# EEZ_DIB_AUX_PS_r2B2.net
KiCad netlist of a schematic drawn in EAGLE
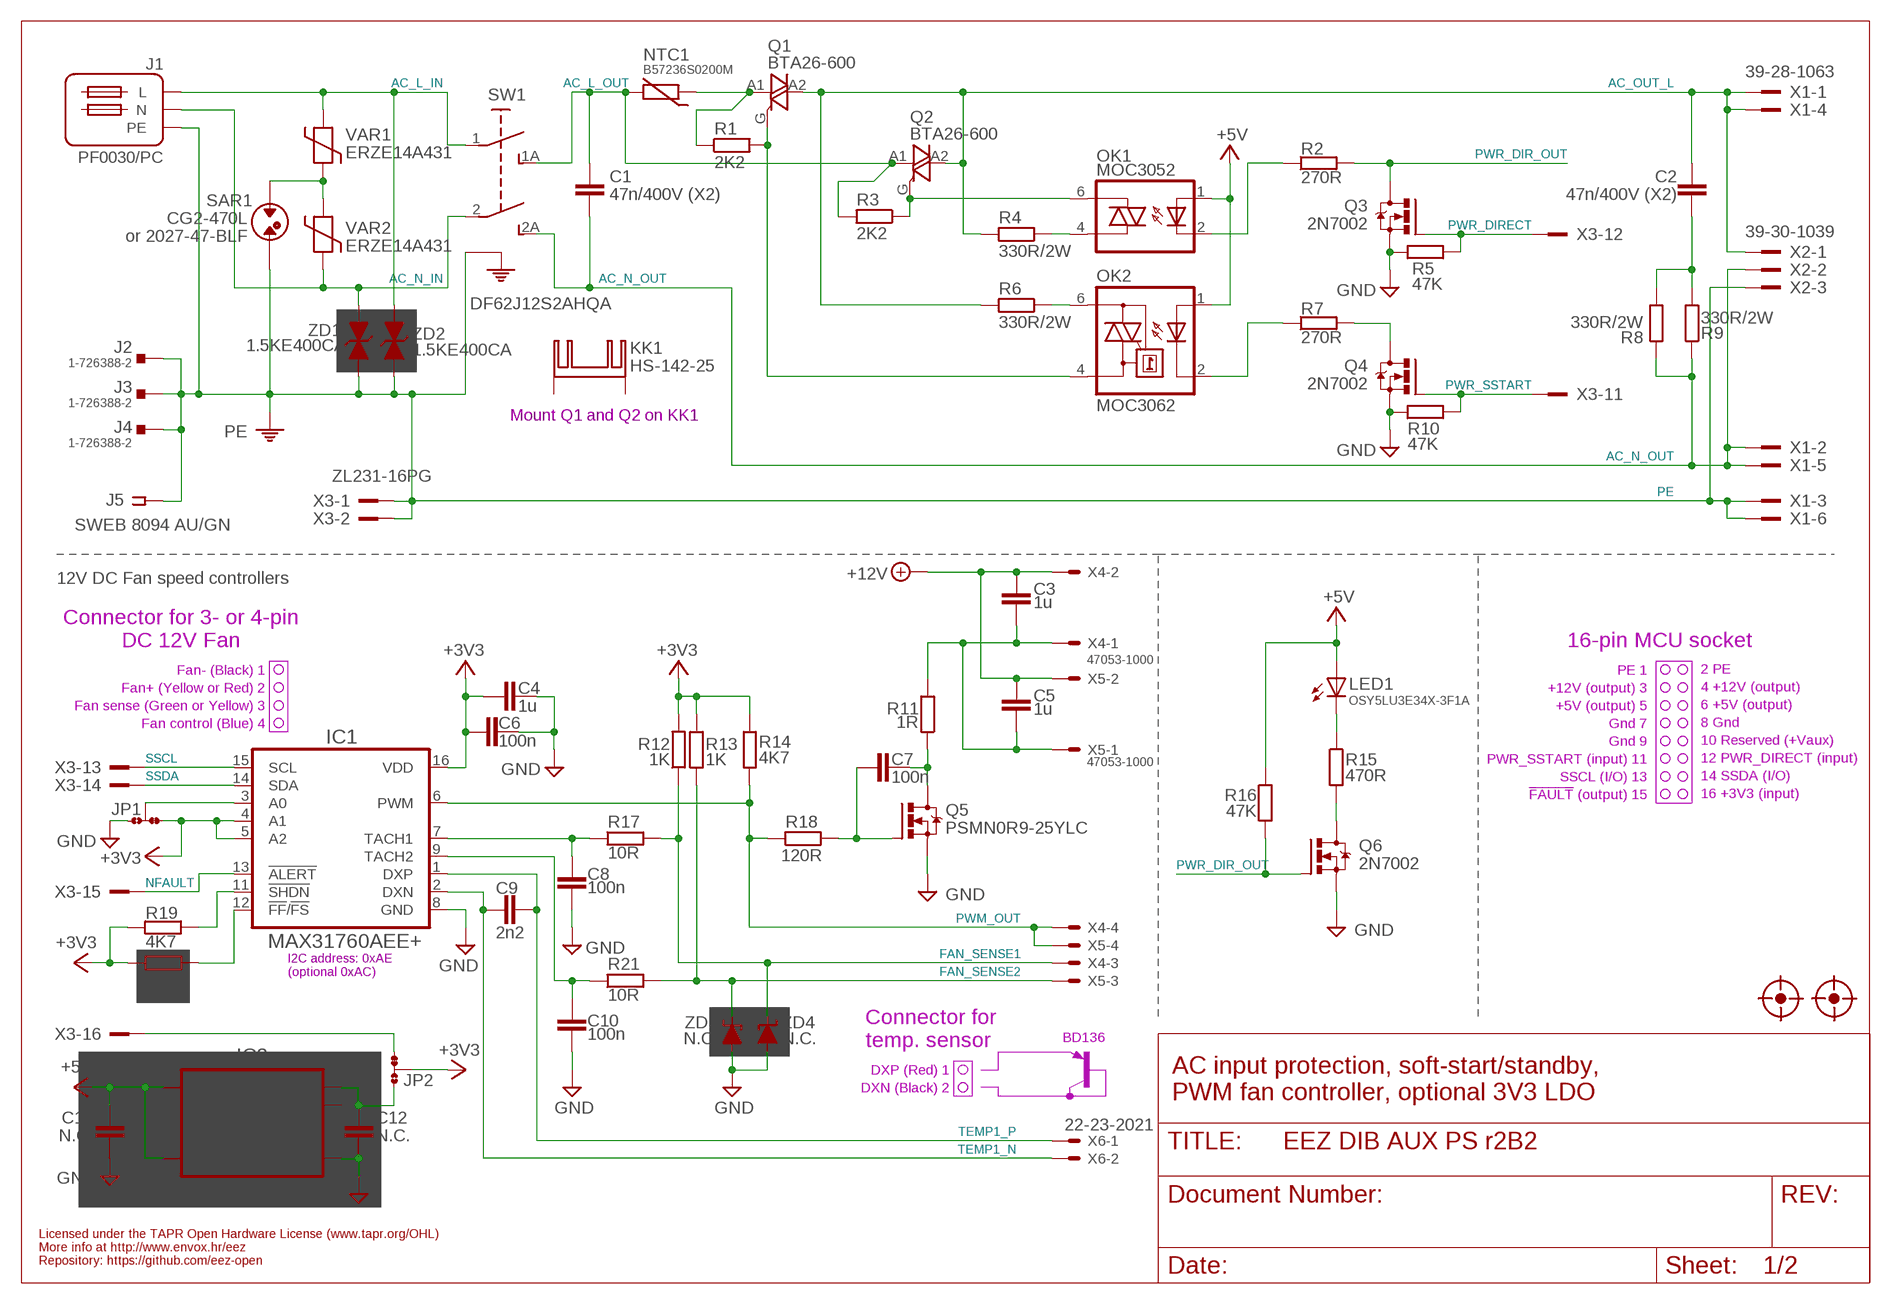
[diagram p0: schematic, sheet 1]
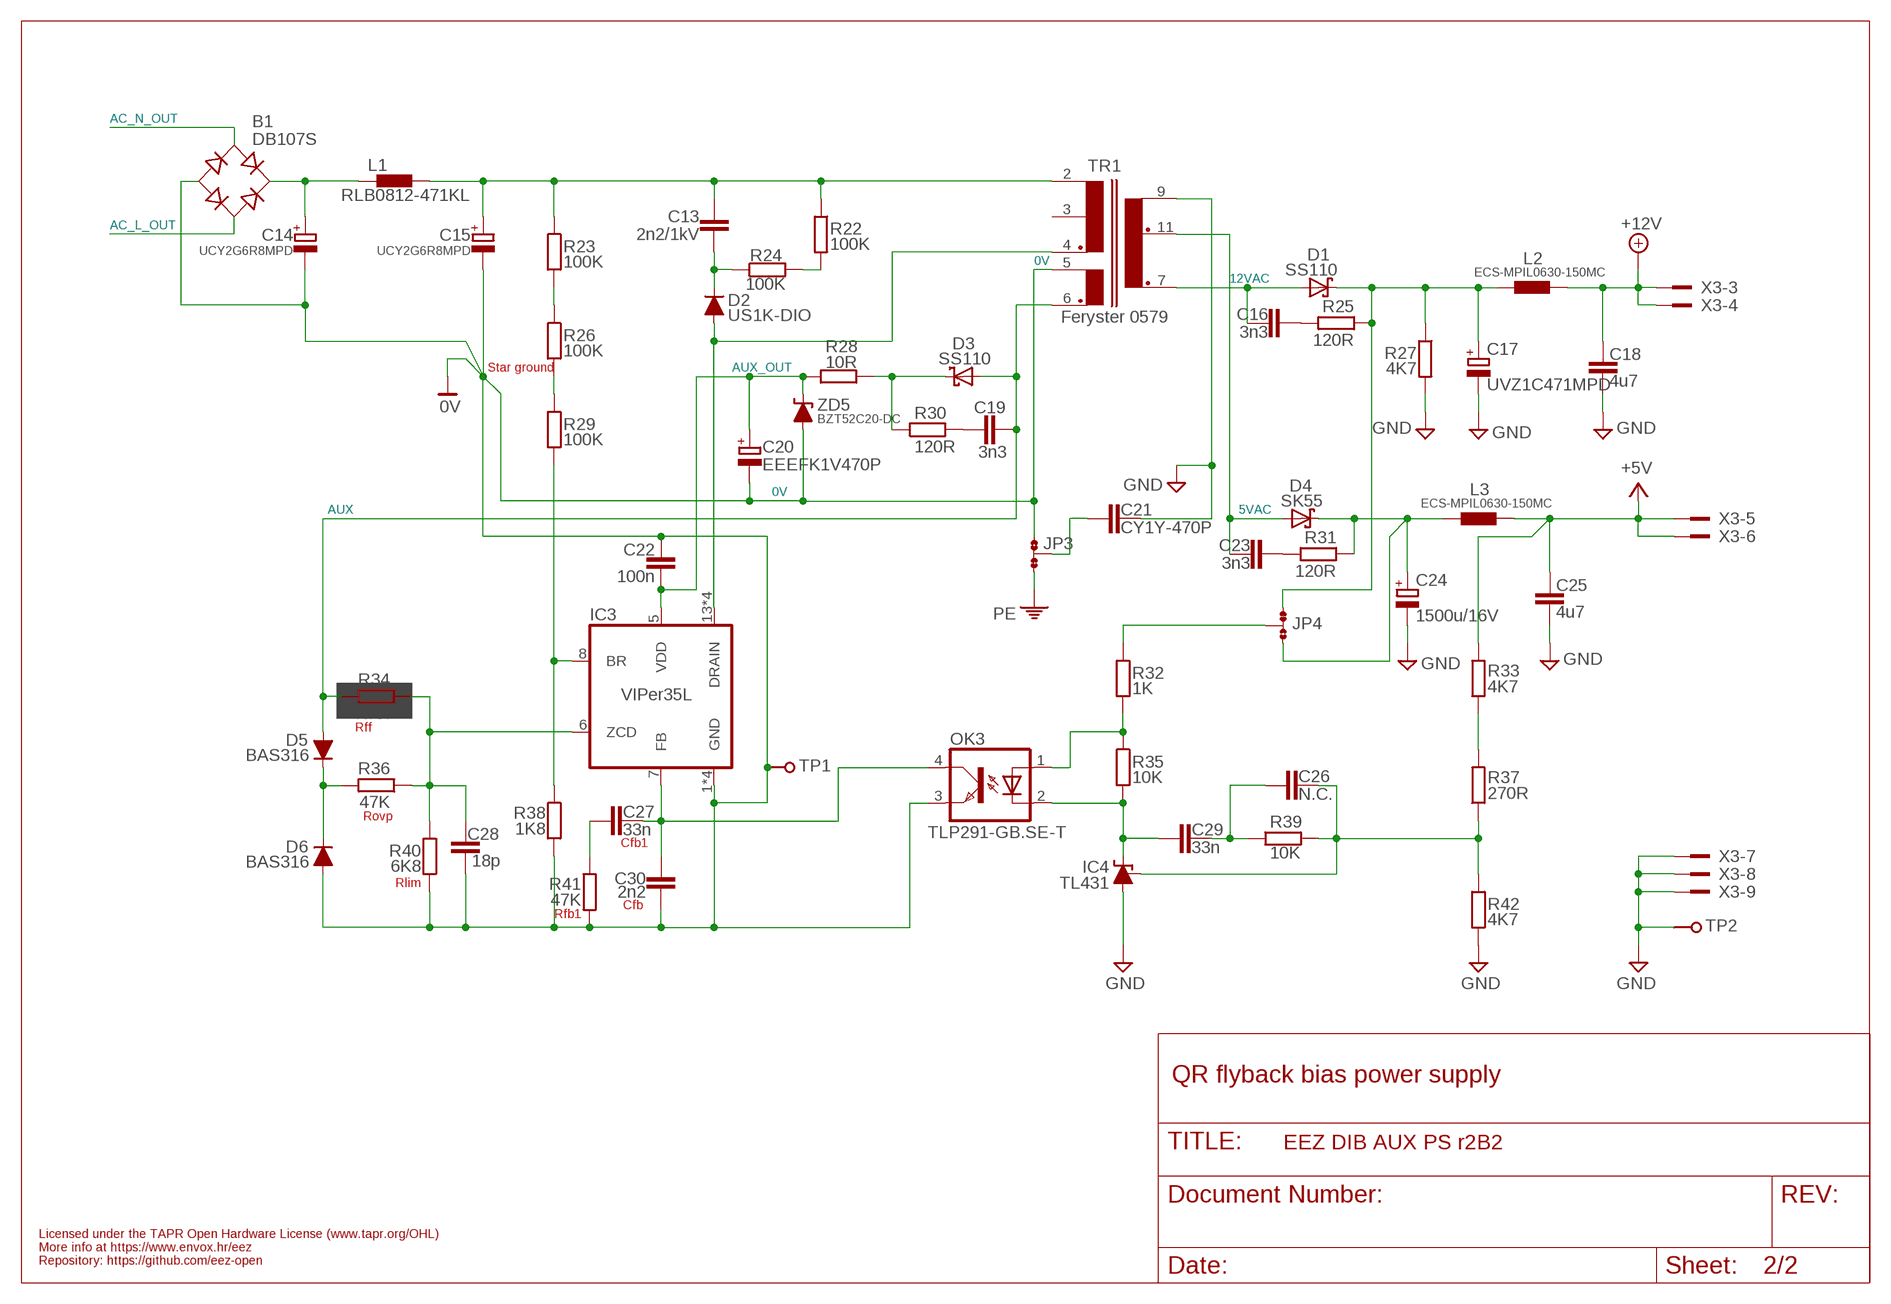
[diagram p1: schematic, sheet 2]

(export (version "E")
  (design (tool "Eeschema 10.0.6"))
  (components
    (comp (ref "B1")
      (value "DB107S")
      (footprint "eagle-import:DBS")
      (libsource (lib "eagle-import") (part "DB?GS107"))
    )
    (comp (ref "C13")
      (value "2n2/1kV")
      (footprint "eagle-import:C1210")
      (libsource (lib "eagle-import") (part "C-EUC1210"))
    )
    (comp (ref "C14")
      (value "UCY2G6R8MPD")
      (footprint "eagle-import:ECAP5_10.5")
      (libsource (lib "eagle-import") (part "ECAP5G_10.5MM"))
    )
    (comp (ref "C15")
      (value "UCY2G6R8MPD")
      (footprint "eagle-import:ECAP5_10.5")
      (libsource (lib "eagle-import") (part "ECAP5G_10.5MM"))
    )
    (comp (ref "C16")
      (value "3n3")
      (footprint "eagle-import:C0805")
      (libsource (lib "eagle-import") (part "C-EUC0805"))
    )
    (comp (ref "C17")
      (value "UVZ1C471MPD")
      (footprint "eagle-import:ECAP3.5_8")
      (libsource (lib "eagle-import") (part "ECAP3.5G_8MM"))
    )
    (comp (ref "C18")
      (value "4u7")
      (footprint "eagle-import:C1210")
      (libsource (lib "eagle-import") (part "C-EUC1210"))
    )
    (comp (ref "C19")
      (value "3n3")
      (footprint "eagle-import:C0805")
      (libsource (lib "eagle-import") (part "C-EUC0805"))
    )
    (comp (ref "C20")
      (value "EEEFK1V470P")
      (footprint "eagle-import:CAPAE660X610N")
      (libsource (lib "eagle-import") (part "ECAPPANASONIC_H"))
    )
    (comp (ref "C21")
      (value "CY1Y-470P")
      (footprint "eagle-import:CY075-032X103")
      (libsource (lib "eagle-import") (part "C-EUCY"))
    )
    (comp (ref "C22")
      (value "100n")
      (footprint "eagle-import:C0603")
      (libsource (lib "eagle-import") (part "C-EUC0603"))
    )
    (comp (ref "C23")
      (value "3n3")
      (footprint "eagle-import:C0805")
      (libsource (lib "eagle-import") (part "C-EUC0805"))
    )
    (comp (ref "C24")
      (value "1500u/16V")
      (footprint "eagle-import:ECAP5_13")
      (libsource (lib "eagle-import") (part "ECAP5G_13MM"))
    )
    (comp (ref "C25")
      (value "4u7")
      (footprint "eagle-import:C1210")
      (libsource (lib "eagle-import") (part "C-EUC1210"))
    )
    (comp (ref "C26")
      (value "N.C.")
      (footprint "eagle-import:C0805")
      (libsource (lib "eagle-import") (part "C-EUC0805"))
    )
    (comp (ref "C27")
      (value "33n")
      (footprint "eagle-import:C0805")
      (libsource (lib "eagle-import") (part "C-EUC0805"))
    )
    (comp (ref "C28")
      (value "18p")
      (footprint "eagle-import:C0603")
      (libsource (lib "eagle-import") (part "C-EUC0603"))
    )
    (comp (ref "C29")
      (value "33n")
      (footprint "eagle-import:C0805")
      (libsource (lib "eagle-import") (part "C-EUC0805"))
    )
    (comp (ref "C30")
      (value "2n2")
      (footprint "eagle-import:C0805")
      (libsource (lib "eagle-import") (part "C-EUC0805"))
    )
    (comp (ref "D1")
      (value "SS110")
      (footprint "eagle-import:SMB")
      (libsource (lib "eagle-import") (part "SCHOTTKYSMB"))
    )
    (comp (ref "D2")
      (value "US1K-DIO")
      (footprint "eagle-import:DO214AA")
      (libsource (lib "eagle-import") (part "DIODEDO214AA"))
    )
    (comp (ref "D3")
      (value "SS110")
      (footprint "eagle-import:SMB")
      (libsource (lib "eagle-import") (part "SCHOTTKYSMB"))
    )
    (comp (ref "D4")
      (value "SK55")
      (footprint "eagle-import:SMB")
      (libsource (lib "eagle-import") (part "SCHOTTKYSMB"))
    )
    (comp (ref "D5")
      (value "BAS316")
      (footprint "eagle-import:SOD323-R")
      (libsource (lib "eagle-import") (part "DIODESOD323R"))
    )
    (comp (ref "D6")
      (value "BAS316")
      (footprint "eagle-import:SOD323-R")
      (libsource (lib "eagle-import") (part "DIODESOD323R"))
    )
    (comp (ref "IC3")
      (value "VIPer35L")
      (footprint "eagle-import:SOIC-16")
      (libsource (lib "eagle-import") (part "VIPER35"))
    )
    (comp (ref "IC4")
      (value "TL431")
      (footprint "eagle-import:SOT103P240X110-3N")
      (libsource (lib "eagle-import") (part "TL431"))
    )
    (comp (ref "JP3")
      (value "JP3-CUT")
      (footprint "eagle-import:JP3-CUT")
      (libsource (lib "eagle-import") (part "JP3-CUT"))
    )
    (comp (ref "JP4")
      (value "JP3-CUT")
      (footprint "eagle-import:JP3-CUT")
      (libsource (lib "eagle-import") (part "JP3-CUT"))
    )
    (comp (ref "L1")
      (value "RLB0812-471KL")
      (footprint "eagle-import:FERSYTER_DSZ6")
      (libsource (lib "eagle-import") (part "FERYSTER_DSZ6"))
    )
    (comp (ref "L2")
      (value "ECS-MPIL0630-150MC")
      (footprint "eagle-import:DE0704")
      (libsource (lib "eagle-import") (part "DE0704"))
    )
    (comp (ref "L3")
      (value "ECS-MPIL0630-150MC")
      (footprint "eagle-import:DE0704")
      (libsource (lib "eagle-import") (part "DE0704"))
    )
    (comp (ref "OK3")
      (value "TLP291-GB.SE-T")
      (footprint "eagle-import:SO4")
      (libsource (lib "eagle-import") (part "TLP291"))
    )
    (comp (ref "R22")
      (value "100K")
      (footprint "eagle-import:R1206")
      (libsource (lib "eagle-import") (part "R-EU_R1206"))
    )
    (comp (ref "R23")
      (value "100K")
      (footprint "eagle-import:R1206")
      (libsource (lib "eagle-import") (part "R-EU_R1206"))
    )
    (comp (ref "R24")
      (value "100K")
      (footprint "eagle-import:R1206")
      (libsource (lib "eagle-import") (part "R-EU_R1206"))
    )
    (comp (ref "R25")
      (value "120R")
      (footprint "eagle-import:R0805")
      (libsource (lib "eagle-import") (part "R-EU_R0805"))
    )
    (comp (ref "R26")
      (value "100K")
      (footprint "eagle-import:R1206")
      (libsource (lib "eagle-import") (part "R-EU_R1206"))
    )
    (comp (ref "R27")
      (value "4K7")
      (footprint "eagle-import:R0805")
      (libsource (lib "eagle-import") (part "R-EU_R0805"))
    )
    (comp (ref "R28")
      (value "10R")
      (footprint "eagle-import:R0805")
      (libsource (lib "eagle-import") (part "R-EU_R0805"))
    )
    (comp (ref "R29")
      (value "100K")
      (footprint "eagle-import:R1206")
      (libsource (lib "eagle-import") (part "R-EU_R1206"))
    )
    (comp (ref "R30")
      (value "120R")
      (footprint "eagle-import:R0805")
      (libsource (lib "eagle-import") (part "R-EU_R0805"))
    )
    (comp (ref "R31")
      (value "120R")
      (footprint "eagle-import:R0805")
      (libsource (lib "eagle-import") (part "R-EU_R0805"))
    )
    (comp (ref "R32")
      (value "1K")
      (footprint "eagle-import:R0805")
      (libsource (lib "eagle-import") (part "R-EU_R0805"))
    )
    (comp (ref "R33")
      (value "4K7")
      (footprint "eagle-import:R0805")
      (libsource (lib "eagle-import") (part "R-EU_R0805"))
    )
    (comp (ref "R34")
      (value "N.C.")
      (footprint "eagle-import:R0805")
      (libsource (lib "eagle-import") (part "R-EU_R0805"))
    )
    (comp (ref "R35")
      (value "10K")
      (footprint "eagle-import:R0805")
      (libsource (lib "eagle-import") (part "R-EU_R0805"))
    )
    (comp (ref "R36")
      (value "47K")
      (footprint "eagle-import:R0805")
      (libsource (lib "eagle-import") (part "R-EU_R0805"))
    )
    (comp (ref "R37")
      (value "270R")
      (footprint "eagle-import:R0805")
      (libsource (lib "eagle-import") (part "R-EU_R0805"))
    )
    (comp (ref "R38")
      (value "1K8")
      (footprint "eagle-import:R0805")
      (libsource (lib "eagle-import") (part "R-EU_R0805"))
    )
    (comp (ref "R39")
      (value "10K")
      (footprint "eagle-import:R0805")
      (libsource (lib "eagle-import") (part "R-EU_R0805"))
    )
    (comp (ref "R40")
      (value "6K8")
      (footprint "eagle-import:R0805")
      (libsource (lib "eagle-import") (part "R-EU_R0805"))
    )
    (comp (ref "R41")
      (value "47K")
      (footprint "eagle-import:R0805")
      (libsource (lib "eagle-import") (part "R-EU_R0805"))
    )
    (comp (ref "R42")
      (value "4K7")
      (footprint "eagle-import:R0805")
      (libsource (lib "eagle-import") (part "R-EU_R0805"))
    )
    (comp (ref "TP1")
      (value "PCB_TEST_TABSHIELD")
      (footprint "eagle-import:PCB_SHIELD_TAB")
      (libsource (lib "eagle-import") (part "PCB_TEST_TABSHIELD"))
    )
    (comp (ref "TP2")
      (value "PCB_TEST_TABSHIELD")
      (footprint "eagle-import:PCB_SHIELD_TAB")
      (libsource (lib "eagle-import") (part "PCB_TEST_TABSHIELD"))
    )
    (comp (ref "TR1")
      (value "Feryster 0579")
      (footprint "eagle-import:FERYSTER_0579")
      (libsource (lib "eagle-import") (part "FERYSTER_0579"))
    )
    (comp (ref "X3")
      (value "ZL231-16PG")
      (footprint "eagle-import:IDC-16PIN")
      (libsource (lib "eagle-import") (part "IDC-16PIN"))
    )
    (comp (ref "ZD5")
      (value "BZT52C20-DC")
      (footprint "eagle-import:SOD123")
      (libsource (lib "eagle-import") (part "ZENER-DIODESOD123"))
    )
    (comp (ref "C1")
      (value "47n/400V (X2)")
      (footprint "eagle-import:C102-054X133")
      (libsource (lib "eagle-import") (part "C-EU102-054X133"))
    )
    (comp (ref "C2")
      (value "47n/400V (X2)")
      (footprint "eagle-import:C102-054X133")
      (libsource (lib "eagle-import") (part "C-EU102-054X133"))
    )
    (comp (ref "C3")
      (value "1u")
      (footprint "eagle-import:C0805")
      (libsource (lib "eagle-import") (part "C-EUC0805"))
    )
    (comp (ref "C4")
      (value "1u")
      (footprint "eagle-import:C0805")
      (libsource (lib "eagle-import") (part "C-EUC0805"))
    )
    (comp (ref "C5")
      (value "1u")
      (footprint "eagle-import:C0805")
      (libsource (lib "eagle-import") (part "C-EUC0805"))
    )
    (comp (ref "C6")
      (value "100n")
      (footprint "eagle-import:C0603")
      (libsource (lib "eagle-import") (part "C-EUC0603"))
    )
    (comp (ref "C7")
      (value "100n")
      (footprint "eagle-import:C0805")
      (libsource (lib "eagle-import") (part "C-EUC0805"))
    )
    (comp (ref "C8")
      (value "100n")
      (footprint "eagle-import:C0603")
      (libsource (lib "eagle-import") (part "C-EUC0603"))
    )
    (comp (ref "C9")
      (value "2n2")
      (footprint "eagle-import:C0805")
      (libsource (lib "eagle-import") (part "C-EUC0805"))
    )
    (comp (ref "C10")
      (value "100n")
      (footprint "eagle-import:C0603")
      (libsource (lib "eagle-import") (part "C-EUC0603"))
    )
    (comp (ref "C11")
      (value "N.C.")
      (footprint "eagle-import:C0805")
      (libsource (lib "eagle-import") (part "C-EUC0805"))
    )
    (comp (ref "C12")
      (value "N.C.")
      (footprint "eagle-import:C0805")
      (libsource (lib "eagle-import") (part "C-EUC0805"))
    )
    (comp (ref "FM1")
      (value "FIDUCIAL")
      (footprint "eagle-import:FIDUCIAL")
      (libsource (lib "eagle-import") (part "FIDUCIAL"))
    )
    (comp (ref "FM2")
      (value "FIDUCIAL")
      (footprint "eagle-import:FIDUCIAL")
      (libsource (lib "eagle-import") (part "FIDUCIAL"))
    )
    (comp (ref "IC1")
      (value "MAX31760AEE+")
      (footprint "eagle-import:DBQ16")
      (libsource (lib "eagle-import") (part "MAX31760AEE+"))
    )
    (comp (ref "IC2")
      (value "LP2985")
      (footprint "eagle-import:SOT95P270X145-5N")
      (libsource (lib "eagle-import") (part "LP2985"))
    )
    (comp (ref "J1")
      (value "PF0030/PC")
      (footprint "eagle-import:PF0030_PC")
      (libsource (lib "eagle-import") (part "PF0030/PC"))
    )
    (comp (ref "J2")
      (value "1-726388-2")
      (footprint "eagle-import:PCB_TAB-4.8MM")
      (libsource (lib "eagle-import") (part "PCB_TAB4.8MM"))
    )
    (comp (ref "J3")
      (value "1-726388-2")
      (footprint "eagle-import:PCB_TAB-4.8MM")
      (libsource (lib "eagle-import") (part "PCB_TAB4.8MM"))
    )
    (comp (ref "J4")
      (value "1-726388-2")
      (footprint "eagle-import:PCB_TAB-4.8MM")
      (libsource (lib "eagle-import") (part "PCB_TAB4.8MM"))
    )
    (comp (ref "J5")
      (value "SWEB 8094 AU/GN")
      (footprint "eagle-import:S16N-PC")
      (libsource (lib "eagle-import") (part "BINDING_POSTCLIFF"))
    )
    (comp (ref "JP1")
      (value "JP3-CUT")
      (footprint "eagle-import:JP3-CUT")
      (libsource (lib "eagle-import") (part "JP3-CUT"))
    )
    (comp (ref "JP2")
      (value "JP3-CUT")
      (footprint "eagle-import:JP3-CUT")
      (libsource (lib "eagle-import") (part "JP3-CUT"))
    )
    (comp (ref "KK1")
      (value "HS-142-25")
      (footprint "eagle-import:SK129")
      (libsource (lib "eagle-import") (part "SK129-PAD"))
    )
    (comp (ref "LED1")
      (value "OSY5LU3E34X-3F1A")
      (footprint "eagle-import:OSG8")
      (libsource (lib "eagle-import") (part "LEDOSG8"))
    )
    (comp (ref "NTC1")
      (value "B57236S0200M")
      (footprint "eagle-import:NTC_11.5X6_RM5")
      (libsource (lib "eagle-import") (part "NTC11.5X6"))
    )
    (comp (ref "OK1")
      (value "MOC3052")
      (footprint "eagle-import:DIL6-SMD")
      (libsource (lib "eagle-import") (part "MOC305X"))
    )
    (comp (ref "OK2")
      (value "MOC3062")
      (footprint "eagle-import:DIL6-SMD")
      (fields
        (field (name "MF") "FAIRCHILD SEMICONDUCTOR")
        (field (name "MPN") "MOC3033S-M")
        (field (name "MF_1") "FAIRCHILD SEMICONDUCTOR")
        (field (name "MPN_1") "MOC3033S-M")
        (field (name "OC_FARNELL") "unknown")
        (field (name "OC_NEWARK") "05C2878")
      )
      (libsource (lib "eagle-import") (part "MOC30S33"))
    )
    (comp (ref "Q1")
      (value "BTA26-600")
      (footprint "eagle-import:TOP3S-1")
      (libsource (lib "eagle-import") (part "BTA26-V"))
    )
    (comp (ref "Q2")
      (value "BTA26-600")
      (footprint "eagle-import:TOP3S-1")
      (libsource (lib "eagle-import") (part "BTA26-V"))
    )
    (comp (ref "Q3")
      (value "2N7002")
      (footprint "eagle-import:SOT103P240X110-3N")
      (fields (field (name "MPN") "2N7002-7-F"))
      (libsource (lib "eagle-import") (part "2N7002"))
    )
    (comp (ref "Q4")
      (value "2N7002")
      (footprint "eagle-import:SOT103P240X110-3N")
      (fields (field (name "MPN") "2N7002-7-F"))
      (libsource (lib "eagle-import") (part "2N7002"))
    )
    (comp (ref "Q5")
      (value "PSMN0R9-25YLC")
      (footprint "eagle-import:SOT669")
      (libsource (lib "eagle-import") (part "N-MOSFETLFPAK"))
    )
    (comp (ref "Q6")
      (value "2N7002")
      (footprint "eagle-import:SOT103P240X110-3N")
      (fields
        (field (name "MPN") "2N7002-7-F")
        (field (name "MPN_1") "2N7002-7-F")
        (field (name "OC_FARNELL") "1713823")
        (field (name "OC_NEWARK") "25R5679")
        (field (name "PACKAGE") "SOT-23-3")
        (field (name "SUPPLIER") "DIODES INC.")
      )
      (libsource (lib "eagle-import") (part "2N7002"))
    )
    (comp (ref "R1")
      (value "2K2")
      (footprint "eagle-import:R0805")
      (libsource (lib "eagle-import") (part "R-EU_R0805"))
    )
    (comp (ref "R2")
      (value "270R")
      (footprint "eagle-import:R0805")
      (libsource (lib "eagle-import") (part "R-EU_R0805"))
    )
    (comp (ref "R3")
      (value "2K2")
      (footprint "eagle-import:R0805")
      (libsource (lib "eagle-import") (part "R-EU_R0805"))
    )
    (comp (ref "R4")
      (value "330R/2W")
      (footprint "eagle-import:R2512")
      (libsource (lib "eagle-import") (part "R-EU_R2512"))
    )
    (comp (ref "R5")
      (value "47K")
      (footprint "eagle-import:R0805")
      (libsource (lib "eagle-import") (part "R-EU_R0805"))
    )
    (comp (ref "R6")
      (value "330R/2W")
      (footprint "eagle-import:R2512")
      (libsource (lib "eagle-import") (part "R-EU_R2512"))
    )
    (comp (ref "R7")
      (value "270R")
      (footprint "eagle-import:R0805")
      (libsource (lib "eagle-import") (part "R-EU_R0805"))
    )
    (comp (ref "R8")
      (value "330R/2W")
      (footprint "eagle-import:R2512")
      (libsource (lib "eagle-import") (part "R-EU_R2512"))
    )
    (comp (ref "R9")
      (value "330R/2W")
      (footprint "eagle-import:R2512")
      (libsource (lib "eagle-import") (part "R-EU_R2512"))
    )
    (comp (ref "R10")
      (value "47K")
      (footprint "eagle-import:R0805")
      (libsource (lib "eagle-import") (part "R-EU_R0805"))
    )
    (comp (ref "R11")
      (value "1R")
      (footprint "eagle-import:R0805")
      (libsource (lib "eagle-import") (part "R-EU_R0805"))
    )
    (comp (ref "R12")
      (value "1K")
      (footprint "eagle-import:R0805")
      (libsource (lib "eagle-import") (part "R-EU_R0805"))
    )
    (comp (ref "R13")
      (value "1K")
      (footprint "eagle-import:R0805")
      (libsource (lib "eagle-import") (part "R-EU_R0805"))
    )
    (comp (ref "R14")
      (value "4K7")
      (footprint "eagle-import:R0805")
      (libsource (lib "eagle-import") (part "R-EU_R0805"))
    )
    (comp (ref "R15")
      (value "470R")
      (footprint "eagle-import:R0805")
      (libsource (lib "eagle-import") (part "R-EU_R0805"))
    )
    (comp (ref "R16")
      (value "47K")
      (footprint "eagle-import:R0805")
      (libsource (lib "eagle-import") (part "R-EU_R0805"))
    )
    (comp (ref "R17")
      (value "10R")
      (footprint "eagle-import:R0805")
      (libsource (lib "eagle-import") (part "R-EU_R0805"))
    )
    (comp (ref "R18")
      (value "120R")
      (footprint "eagle-import:R0805")
      (libsource (lib "eagle-import") (part "R-EU_R0805"))
    )
    (comp (ref "R19")
      (value "4K7")
      (footprint "eagle-import:R0805")
      (libsource (lib "eagle-import") (part "R-EU_R0805"))
    )
    (comp (ref "R20")
      (value "N.C.")
      (footprint "eagle-import:R0805")
      (libsource (lib "eagle-import") (part "R-EU_R0805"))
    )
    (comp (ref "R21")
      (value "10R")
      (footprint "eagle-import:R0805")
      (libsource (lib "eagle-import") (part "R-EU_R0805"))
    )
    (comp (ref "SAR1")
      (value "CG2-470L")
      (footprint "eagle-import:SAR")
      (libsource (lib "eagle-import") (part "SAR"))
    )
    (comp (ref "SW1")
      (value "DF62J12S2AHQA")
      (footprint "eagle-import:DF62J12S2")
      (libsource (lib "eagle-import") (part "DF62J12S2AHQA"))
    )
    (comp (ref "VAR1")
      (value "ERZE14A431")
      (footprint "eagle-import:VARISTOR_13MM")
      (libsource (lib "eagle-import") (part "VARISTOR-13"))
    )
    (comp (ref "VAR2")
      (value "ERZE14A431")
      (footprint "eagle-import:VARISTOR_13MM")
      (libsource (lib "eagle-import") (part "VARISTOR-13"))
    )
    (comp (ref "X1")
      (value "39-28-1063")
      (footprint "eagle-import:MINIFIT_5566-06A_CRE")
      (libsource (lib "eagle-import") (part "MINIFIT_5566-06A-CRE"))
    )
    (comp (ref "X2")
      (value "39-30-1039")
      (footprint "eagle-import:MINIFIT_39301039_CRE")
      (libsource (lib "eagle-import") (part "MINIFIT_39301039-CREEPAGE"))
    )
    (comp (ref "X4")
      (value "47053-1000")
      (footprint "eagle-import:47053-1000")
      (libsource (lib "eagle-import") (part "47053-1000"))
    )
    (comp (ref "X5")
      (value "47053-1000")
      (footprint "eagle-import:47053-1000")
      (libsource (lib "eagle-import") (part "47053-1000"))
    )
    (comp (ref "X6")
      (value "22-23-2021")
      (footprint "eagle-import:22-23-2021")
      (fields (field (name "MF") "MOLEX"))
      (libsource (lib "eagle-import") (part "22-23-2021"))
    )
    (comp (ref "ZD1")
      (value "1.5KE400CA")
      (footprint "eagle-import:DO201-BIDIR")
      (libsource (lib "eagle-import") (part "1.5KE-BIDIR"))
    )
    (comp (ref "ZD2")
      (value "1.5KE400CA")
      (footprint "eagle-import:DO201-BIDIR")
      (libsource (lib "eagle-import") (part "1.5KE-BIDIR"))
    )
    (comp (ref "ZD3")
      (value "N.C.")
      (footprint "eagle-import:SOD123")
      (libsource (lib "eagle-import") (part "ZENER-DIODESOD123"))
    )
    (comp (ref "ZD4")
      (value "N.C.")
      (footprint "eagle-import:SOD123")
      (libsource (lib "eagle-import") (part "ZENER-DIODESOD123"))
    )
  )
  (nets
    (net (code "1") (name "+3V3") (class "Default")
      (node (ref "C4") (pin "2") (pinfunction "2_2") (pintype "passive"))
      (node (ref "C6") (pin "2") (pinfunction "2_2") (pintype "passive"))
      (node (ref "IC1") (pin "16") (pinfunction "VDD_16") (pintype "power_in"))
      (node (ref "IC1") (pin "4") (pinfunction "A1_4") (pintype "input"))
      (node (ref "IC1") (pin "5") (pinfunction "A2_5") (pintype "input"))
      (node (ref "JP1") (pin "NC") (pinfunction "NC_NC") (pintype "passive"))
      (node (ref "JP2") (pin "COM") (pinfunction "COM_COM") (pintype "passive"))
      (node (ref "R12") (pin "2") (pinfunction "2_2") (pintype "passive"))
      (node (ref "R13") (pin "2") (pinfunction "2_2") (pintype "passive"))
      (node (ref "R14") (pin "1") (pinfunction "1_1") (pintype "passive"))
      (node (ref "R19") (pin "2") (pinfunction "2_2") (pintype "passive"))
      (node (ref "R20") (pin "2") (pinfunction "2_2") (pintype "passive"))
    )
    (net (code "2") (name "+5V") (class "Default")
      (node (ref "C11") (pin "1") (pinfunction "1_1") (pintype "passive"))
      (node (ref "C25") (pin "1") (pinfunction "1_1") (pintype "passive"))
      (node (ref "IC2") (pin "1") (pinfunction "IN_1") (pintype "input"))
      (node (ref "IC2") (pin "3") (pinfunction "ON/~{OFF}_3") (pintype "input"))
      (node (ref "L3") (pin "2") (pinfunction "2_2") (pintype "passive"))
      (node (ref "LED1") (pin "A") (pinfunction "A_A") (pintype "passive"))
      (node (ref "OK1") (pin "1") (pinfunction "A_1") (pintype "passive"))
      (node (ref "OK2") (pin "1") (pinfunction "A_1") (pintype "passive"))
      (node (ref "R16") (pin "1") (pinfunction "1_1") (pintype "passive"))
      (node (ref "R33") (pin "2") (pinfunction "2_2") (pintype "passive"))
      (node (ref "X3") (pin "5") (pinfunction "1_5") (pintype "passive"))
      (node (ref "X3") (pin "6") (pinfunction "1_6") (pintype "passive"))
    )
    (net (code "3") (name "+12V") (class "Default")
      (node (ref "C18") (pin "1") (pinfunction "1_1") (pintype "passive"))
      (node (ref "C3") (pin "1") (pinfunction "1_1") (pintype "passive"))
      (node (ref "C5") (pin "1") (pinfunction "1_1") (pintype "passive"))
      (node (ref "L2") (pin "2") (pinfunction "2_2") (pintype "passive"))
      (node (ref "X3") (pin "3") (pinfunction "1_3") (pintype "passive"))
      (node (ref "X3") (pin "4") (pinfunction "1_4") (pintype "passive"))
      (node (ref "X4") (pin "2") (pinfunction "S_2") (pintype "passive"))
      (node (ref "X5") (pin "2") (pinfunction "S_2") (pintype "passive"))
    )
    (net (code "4") (name "0V") (class "Default")
      (node (ref "B1") (pin "-") (pinfunction "-_-") (pintype "passive"))
      (node (ref "C14") (pin "-") (pinfunction "-_-") (pintype "passive"))
      (node (ref "C15") (pin "-") (pinfunction "-_-") (pintype "passive"))
      (node (ref "C20") (pin "2") (pinfunction "-_2") (pintype "passive"))
      (node (ref "C22") (pin "1") (pinfunction "1_1") (pintype "passive"))
      (node (ref "C28") (pin "2") (pinfunction "2_2") (pintype "passive"))
      (node (ref "C30") (pin "2") (pinfunction "2_2") (pintype "passive"))
      (node (ref "D6") (pin "A") (pinfunction "A_A") (pintype "passive"))
      (node (ref "IC3") (pin "1") (pinfunction "GND_1") (pintype "passive"))
      (node (ref "IC3") (pin "2") (pinfunction "GND_2") (pintype "passive"))
      (node (ref "IC3") (pin "3") (pinfunction "GND_3") (pintype "passive"))
      (node (ref "IC3") (pin "4") (pinfunction "GND_4") (pintype "passive"))
      (node (ref "JP3") (pin "NO") (pinfunction "NO_NO") (pintype "passive"))
      (node (ref "OK3") (pin "3") (pinfunction "EMIT_3") (pintype "passive"))
      (node (ref "R38") (pin "2") (pinfunction "2_2") (pintype "passive"))
      (node (ref "R40") (pin "1") (pinfunction "1_1") (pintype "passive"))
      (node (ref "R41") (pin "2") (pinfunction "2_2") (pintype "passive"))
      (node (ref "TP1") (pin "1") (pinfunction "P$1_1") (pintype "bidirectional"))
      (node (ref "TR1") (pin "5") (pinfunction "AUX_5") (pintype "passive"))
      (node (ref "ZD5") (pin "A") (pinfunction "A_A") (pintype "passive"))
    )
    (net (code "5") (name "5VAC") (class "Default")
      (node (ref "C23") (pin "2") (pinfunction "2_2") (pintype "passive"))
      (node (ref "D4") (pin "A") (pinfunction "A_A") (pintype "passive"))
      (node (ref "TR1") (pin "11") (pinfunction "S1_DOT_11") (pintype "passive"))
    )
    (net (code "6") (name "12VAC") (class "Default")
      (node (ref "C16") (pin "2") (pinfunction "2_2") (pintype "passive"))
      (node (ref "D1") (pin "A") (pinfunction "A_A") (pintype "passive"))
      (node (ref "TR1") (pin "7") (pinfunction "S2_DOT_7") (pintype "passive"))
    )
    (net (code "7") (name "AC_L_IN") (class "Default")
      (node (ref "J1") (pin "L") (pinfunction "L_L") (pintype "bidirectional"))
      (node (ref "SW1") (pin "1") (pinfunction "P_1") (pintype "passive"))
      (node (ref "VAR1") (pin "2") (pinfunction "P$2_2") (pintype "bidirectional"))
      (node (ref "ZD2") (pin "A") (pinfunction "2_A") (pintype "passive"))
    )
    (net (code "8") (name "AC_L_OUT") (class "Default")
      (node (ref "B1") (pin "AC2") (pinfunction "AC2_AC2") (pintype "passive"))
      (node (ref "C1") (pin "1") (pinfunction "1_1") (pintype "passive"))
      (node (ref "NTC1") (pin "1") (pinfunction "P$1_1") (pintype "bidirectional"))
      (node (ref "Q2") (pin "A1") (pinfunction "A1_A1") (pintype "passive"))
      (node (ref "R3") (pin "2") (pinfunction "2_2") (pintype "passive"))
      (node (ref "SW1") (pin "1A") (pinfunction "S_1A") (pintype "passive"))
    )
    (net (code "9") (name "AC_N_IN") (class "Default")
      (node (ref "J1") (pin "N") (pinfunction "N_N") (pintype "bidirectional"))
      (node (ref "SW1") (pin "2") (pinfunction "P1_2") (pintype "passive"))
      (node (ref "VAR2") (pin "1") (pinfunction "P$1_1") (pintype "bidirectional"))
      (node (ref "ZD1") (pin "A") (pinfunction "2_A") (pintype "passive"))
    )
    (net (code "10") (name "AC_N_OUT") (class "Default")
      (node (ref "B1") (pin "AC1") (pinfunction "AC1_AC1") (pintype "passive"))
      (node (ref "C1") (pin "2") (pinfunction "2_2") (pintype "passive"))
      (node (ref "R8") (pin "1") (pinfunction "1_1") (pintype "passive"))
      (node (ref "R9") (pin "1") (pinfunction "1_1") (pintype "passive"))
      (node (ref "SW1") (pin "2A") (pinfunction "S1_2A") (pintype "passive"))
      (node (ref "X1") (pin "2") (pinfunction "1_2") (pintype "passive"))
      (node (ref "X1") (pin "5") (pinfunction "1_5") (pintype "passive"))
      (node (ref "X2") (pin "2") (pinfunction "1_2") (pintype "passive"))
    )
    (net (code "11") (name "AC_OUT_L") (class "Default")
      (node (ref "C2") (pin "1") (pinfunction "1_1") (pintype "passive"))
      (node (ref "Q1") (pin "A2") (pinfunction "A2_A2") (pintype "passive"))
      (node (ref "Q2") (pin "A2") (pinfunction "A2_A2") (pintype "passive"))
      (node (ref "R4") (pin "2") (pinfunction "2_2") (pintype "passive"))
      (node (ref "R6") (pin "2") (pinfunction "2_2") (pintype "passive"))
      (node (ref "X1") (pin "1") (pinfunction "1_1") (pintype "passive"))
      (node (ref "X1") (pin "4") (pinfunction "1_4") (pintype "passive"))
      (node (ref "X2") (pin "1") (pinfunction "1_1") (pintype "passive"))
    )
    (net (code "12") (name "AUX") (class "Default")
      (node (ref "C19") (pin "2") (pinfunction "2_2") (pintype "passive"))
      (node (ref "D3") (pin "A") (pinfunction "A_A") (pintype "passive"))
      (node (ref "D5") (pin "A") (pinfunction "A_A") (pintype "passive"))
      (node (ref "R34") (pin "2") (pinfunction "2_2") (pintype "passive"))
      (node (ref "TR1") (pin "6") (pinfunction "AUX_DOT_6") (pintype "passive"))
    )
    (net (code "13") (name "AUX_OUT") (class "Default")
      (node (ref "C20") (pin "1") (pinfunction "+_1") (pintype "passive"))
      (node (ref "C22") (pin "2") (pinfunction "2_2") (pintype "passive"))
      (node (ref "IC3") (pin "5") (pinfunction "VDD_5") (pintype "power_in"))
      (node (ref "R28") (pin "2") (pinfunction "2_2") (pintype "passive"))
      (node (ref "ZD5") (pin "C") (pinfunction "C_C") (pintype "passive"))
    )
    (net (code "14") (name "FAN_SENSE1") (class "Default")
      (node (ref "R12") (pin "1") (pinfunction "1_1") (pintype "passive"))
      (node (ref "R17") (pin "2") (pinfunction "2_2") (pintype "passive"))
      (node (ref "X4") (pin "3") (pinfunction "S_3") (pintype "passive"))
      (node (ref "ZD4") (pin "C") (pinfunction "C_C") (pintype "passive"))
    )
    (net (code "15") (name "FAN_SENSE2") (class "Default")
      (node (ref "R13") (pin "1") (pinfunction "1_1") (pintype "passive"))
      (node (ref "R21") (pin "2") (pinfunction "2_2") (pintype "passive"))
      (node (ref "X5") (pin "3") (pinfunction "S_3") (pintype "passive"))
      (node (ref "ZD3") (pin "C") (pinfunction "C_C") (pintype "passive"))
    )
    (net (code "16") (name "GND") (class "Default")
      (node (ref "C10") (pin "2") (pinfunction "2_2") (pintype "passive"))
      (node (ref "C11") (pin "2") (pinfunction "2_2") (pintype "passive"))
      (node (ref "C12") (pin "2") (pinfunction "2_2") (pintype "passive"))
      (node (ref "C17") (pin "-") (pinfunction "-_-") (pintype "passive"))
      (node (ref "C18") (pin "2") (pinfunction "2_2") (pintype "passive"))
      (node (ref "C21") (pin "2") (pinfunction "2_2") (pintype "passive"))
      (node (ref "C24") (pin "-") (pinfunction "-_-") (pintype "passive"))
      (node (ref "C25") (pin "2") (pinfunction "2_2") (pintype "passive"))
      (node (ref "C4") (pin "1") (pinfunction "1_1") (pintype "passive"))
      (node (ref "C6") (pin "1") (pinfunction "1_1") (pintype "passive"))
      (node (ref "C8") (pin "2") (pinfunction "2_2") (pintype "passive"))
      (node (ref "IC1") (pin "8") (pinfunction "GND_8") (pintype "power_in"))
      (node (ref "IC2") (pin "2") (pinfunction "GND_2") (pintype "passive"))
      (node (ref "IC4") (pin "3") (pinfunction "A_3") (pintype "passive"))
      (node (ref "JP1") (pin "NO") (pinfunction "NO_NO") (pintype "passive"))
      (node (ref "Q3") (pin "2") (pinfunction "S_2") (pintype "passive"))
      (node (ref "Q4") (pin "2") (pinfunction "S_2") (pintype "passive"))
      (node (ref "Q5") (pin "1") (pinfunction "S_1") (pintype "passive"))
      (node (ref "Q5") (pin "2") (pinfunction "S_2") (pintype "passive"))
      (node (ref "Q5") (pin "3") (pinfunction "S_3") (pintype "passive"))
      (node (ref "Q6") (pin "2") (pinfunction "S_2") (pintype "passive"))
      (node (ref "R10") (pin "1") (pinfunction "1_1") (pintype "passive"))
      (node (ref "R27") (pin "2") (pinfunction "2_2") (pintype "passive"))
      (node (ref "R42") (pin "1") (pinfunction "1_1") (pintype "passive"))
      (node (ref "R5") (pin "1") (pinfunction "1_1") (pintype "passive"))
      (node (ref "TP2") (pin "1") (pinfunction "P$1_1") (pintype "bidirectional"))
      (node (ref "TR1") (pin "9") (pinfunction "S_COMM_9") (pintype "passive"))
      (node (ref "X3") (pin "7") (pinfunction "1_7") (pintype "passive"))
      (node (ref "X3") (pin "8") (pinfunction "1_8") (pintype "passive"))
      (node (ref "X3") (pin "9") (pinfunction "1_9") (pintype "passive"))
      (node (ref "ZD3") (pin "A") (pinfunction "A_A") (pintype "passive"))
      (node (ref "ZD4") (pin "A") (pinfunction "A_A") (pintype "passive"))
    )
    (net (code "17") (name "NFAULT") (class "Default")
      (node (ref "IC1") (pin "13") (pinfunction "~{ALERT}_13") (pintype "output"))
      (node (ref "X3") (pin "15") (pinfunction "1_15") (pintype "passive"))
    )
    (net (code "18") (name "Net-(C2-Pad2)") (class "Default")
      (node (ref "C2") (pin "2") (pinfunction "2_2") (pintype "passive"))
      (node (ref "R8") (pin "2") (pinfunction "2_2") (pintype "passive"))
      (node (ref "R9") (pin "2") (pinfunction "2_2") (pintype "passive"))
    )
    (net (code "19") (name "Net-(C13-Pad2)") (class "Default")
      (node (ref "C13") (pin "2") (pinfunction "2_2") (pintype "passive"))
      (node (ref "D2") (pin "C") (pinfunction "C_C") (pintype "passive"))
      (node (ref "R24") (pin "1") (pinfunction "1_1") (pintype "passive"))
    )
    (net (code "20") (name "Net-(C16-Pad1)") (class "Default")
      (node (ref "C16") (pin "1") (pinfunction "1_1") (pintype "passive"))
      (node (ref "R25") (pin "2") (pinfunction "2_2") (pintype "passive"))
    )
    (net (code "21") (name "Net-(C17-Pad+)") (class "Default")
      (node (ref "C17") (pin "+") (pinfunction "+_+") (pintype "passive"))
      (node (ref "D1") (pin "C") (pinfunction "C_C") (pintype "passive"))
      (node (ref "JP4") (pin "NC") (pinfunction "NC_NC") (pintype "passive"))
      (node (ref "L2") (pin "1") (pinfunction "1_1") (pintype "passive"))
      (node (ref "R25") (pin "1") (pinfunction "1_1") (pintype "passive"))
      (node (ref "R27") (pin "1") (pinfunction "1_1") (pintype "passive"))
    )
    (net (code "22") (name "Net-(C19-Pad1)") (class "Default")
      (node (ref "C19") (pin "1") (pinfunction "1_1") (pintype "passive"))
      (node (ref "R30") (pin "2") (pinfunction "2_2") (pintype "passive"))
    )
    (net (code "23") (name "Net-(C21-Pad1)") (class "Default")
      (node (ref "C21") (pin "1") (pinfunction "1_1") (pintype "passive"))
      (node (ref "JP3") (pin "COM") (pinfunction "COM_COM") (pintype "passive"))
    )
    (net (code "24") (name "Net-(C23-Pad1)") (class "Default")
      (node (ref "C23") (pin "1") (pinfunction "1_1") (pintype "passive"))
      (node (ref "R31") (pin "2") (pinfunction "2_2") (pintype "passive"))
    )
    (net (code "25") (name "Net-(C24-Pad+)") (class "Default")
      (node (ref "C24") (pin "+") (pinfunction "+_+") (pintype "passive"))
      (node (ref "D4") (pin "C") (pinfunction "C_C") (pintype "passive"))
      (node (ref "JP4") (pin "NO") (pinfunction "NO_NO") (pintype "passive"))
      (node (ref "L3") (pin "1") (pinfunction "1_1") (pintype "passive"))
      (node (ref "R31") (pin "1") (pinfunction "1_1") (pintype "passive"))
    )
    (net (code "26") (name "Net-(C26-Pad1)") (class "Default")
      (node (ref "C26") (pin "1") (pinfunction "1_1") (pintype "passive"))
      (node (ref "C29") (pin "2") (pinfunction "2_2") (pintype "passive"))
      (node (ref "R39") (pin "1") (pinfunction "1_1") (pintype "passive"))
    )
    (net (code "27") (name "Net-(C27-Pad1)") (class "Default")
      (node (ref "C27") (pin "1") (pinfunction "1_1") (pintype "passive"))
      (node (ref "R41") (pin "1") (pinfunction "1_1") (pintype "passive"))
    )
    (net (code "28") (name "Net-(D3-PadC)") (class "Default")
      (node (ref "D3") (pin "C") (pinfunction "C_C") (pintype "passive"))
      (node (ref "R28") (pin "1") (pinfunction "1_1") (pintype "passive"))
      (node (ref "R30") (pin "1") (pinfunction "1_1") (pintype "passive"))
    )
    (net (code "29") (name "Net-(D5-PadC)") (class "Default")
      (node (ref "D5") (pin "C") (pinfunction "C_C") (pintype "passive"))
      (node (ref "D6") (pin "C") (pinfunction "C_C") (pintype "passive"))
      (node (ref "R36") (pin "2") (pinfunction "2_2") (pintype "passive"))
    )
    (net (code "30") (name "Net-(IC1-A0)") (class "Default")
      (node (ref "IC1") (pin "3") (pinfunction "A0_3") (pintype "input"))
      (node (ref "JP1") (pin "COM") (pinfunction "COM_COM") (pintype "passive"))
    )
    (net (code "31") (name "Net-(IC1-TACH1)") (class "Default")
      (node (ref "C8") (pin "1") (pinfunction "1_1") (pintype "passive"))
      (node (ref "IC1") (pin "7") (pinfunction "TACH1_7") (pintype "input"))
      (node (ref "R17") (pin "1") (pinfunction "1_1") (pintype "passive"))
    )
    (net (code "32") (name "Net-(IC1-TACH2)") (class "Default")
      (node (ref "C10") (pin "1") (pinfunction "1_1") (pintype "passive"))
      (node (ref "IC1") (pin "9") (pinfunction "TACH2_9") (pintype "input"))
      (node (ref "R21") (pin "1") (pinfunction "1_1") (pintype "passive"))
    )
    (net (code "33") (name "Net-(IC1-~{FF}{slash}~{FS})") (class "Default")
      (node (ref "IC1") (pin "12") (pinfunction "~{FF}/~{FS}_12") (pintype "bidirectional"))
      (node (ref "R20") (pin "1") (pinfunction "1_1") (pintype "passive"))
    )
    (net (code "34") (name "Net-(IC1-~{SHDN})") (class "Default")
      (node (ref "IC1") (pin "11") (pinfunction "~{SHDN}_11") (pintype "output"))
      (node (ref "R19") (pin "1") (pinfunction "1_1") (pintype "passive"))
    )
    (net (code "35") (name "Net-(IC2-OUT)") (class "Default")
      (node (ref "C12") (pin "1") (pinfunction "1_1") (pintype "passive"))
      (node (ref "IC2") (pin "5") (pinfunction "OUT_5") (pintype "passive"))
      (node (ref "JP2") (pin "NO") (pinfunction "NO_NO") (pintype "passive"))
    )
    (net (code "36") (name "Net-(IC3-BR)") (class "Default")
      (node (ref "IC3") (pin "8") (pinfunction "BR_8") (pintype "input"))
      (node (ref "R29") (pin "2") (pinfunction "2_2") (pintype "passive"))
      (node (ref "R38") (pin "1") (pinfunction "1_1") (pintype "passive"))
    )
    (net (code "37") (name "Net-(IC3-FB)") (class "Default")
      (node (ref "C27") (pin "2") (pinfunction "2_2") (pintype "passive"))
      (node (ref "C30") (pin "1") (pinfunction "1_1") (pintype "passive"))
      (node (ref "IC3") (pin "7") (pinfunction "FB_7") (pintype "input"))
      (node (ref "OK3") (pin "4") (pinfunction "COL_4") (pintype "passive"))
    )
    (net (code "38") (name "Net-(IC3-ZCD)") (class "Default")
      (node (ref "C28") (pin "1") (pinfunction "1_1") (pintype "passive"))
      (node (ref "IC3") (pin "6") (pinfunction "ZCD_6") (pintype "input"))
      (node (ref "R34") (pin "1") (pinfunction "1_1") (pintype "passive"))
      (node (ref "R36") (pin "1") (pinfunction "1_1") (pintype "passive"))
      (node (ref "R40") (pin "2") (pinfunction "2_2") (pintype "passive"))
    )
    (net (code "39") (name "Net-(IC4-C)") (class "Default")
      (node (ref "C29") (pin "1") (pinfunction "1_1") (pintype "passive"))
      (node (ref "IC4") (pin "1") (pinfunction "C_1") (pintype "passive"))
      (node (ref "OK3") (pin "2") (pinfunction "C_2") (pintype "passive"))
      (node (ref "R35") (pin "2") (pinfunction "2_2") (pintype "passive"))
    )
    (net (code "40") (name "Net-(IC4-REF)") (class "Default")
      (node (ref "C26") (pin "2") (pinfunction "2_2") (pintype "passive"))
      (node (ref "IC4") (pin "2") (pinfunction "REF_2") (pintype "passive"))
      (node (ref "R37") (pin "1") (pinfunction "1_1") (pintype "passive"))
      (node (ref "R39") (pin "2") (pinfunction "2_2") (pintype "passive"))
      (node (ref "R42") (pin "2") (pinfunction "2_2") (pintype "passive"))
    )
    (net (code "41") (name "Net-(JP4-PadCOM)") (class "Default")
      (node (ref "JP4") (pin "COM") (pinfunction "COM_COM") (pintype "passive"))
      (node (ref "R32") (pin "1") (pinfunction "1_1") (pintype "passive"))
    )
    (net (code "42") (name "Net-(L1-1)") (class "Default")
      (node (ref "B1") (pin "+") (pinfunction "+_+") (pintype "passive"))
      (node (ref "C14") (pin "+") (pinfunction "+_+") (pintype "passive"))
      (node (ref "L1") (pin "P$1") (pinfunction "1_P$1") (pintype "passive"))
    )
    (net (code "43") (name "Net-(L1-2)") (class "Default")
      (node (ref "C13") (pin "1") (pinfunction "1_1") (pintype "passive"))
      (node (ref "C15") (pin "+") (pinfunction "+_+") (pintype "passive"))
      (node (ref "L1") (pin "P$2") (pinfunction "2_P$2") (pintype "passive"))
      (node (ref "R22") (pin "1") (pinfunction "1_1") (pintype "passive"))
      (node (ref "R23") (pin "1") (pinfunction "1_1") (pintype "passive"))
      (node (ref "TR1") (pin "2") (pinfunction "P1_2") (pintype "passive"))
    )
    (net (code "44") (name "Net-(LED1-PadC)") (class "Default")
      (node (ref "LED1") (pin "C") (pinfunction "C_C") (pintype "passive"))
      (node (ref "R15") (pin "1") (pinfunction "1_1") (pintype "passive"))
    )
    (net (code "45") (name "Net-(NTC1-P$2)") (class "Default")
      (node (ref "NTC1") (pin "2") (pinfunction "P$2_2") (pintype "bidirectional"))
      (node (ref "Q1") (pin "A1") (pinfunction "A1_A1") (pintype "passive"))
      (node (ref "R1") (pin "1") (pinfunction "1_1") (pintype "passive"))
    )
    (net (code "46") (name "Net-(OK1-A1)") (class "Default")
      (node (ref "OK1") (pin "4") (pinfunction "A1_4") (pintype "passive"))
      (node (ref "R4") (pin "1") (pinfunction "1_1") (pintype "passive"))
    )
    (net (code "47") (name "Net-(OK1-A2)") (class "Default")
      (node (ref "OK1") (pin "6") (pinfunction "A2_6") (pintype "passive"))
      (node (ref "Q2") (pin "G") (pinfunction "G_G") (pintype "passive"))
      (node (ref "R3") (pin "1") (pinfunction "1_1") (pintype "passive"))
    )
    (net (code "48") (name "Net-(OK1-C)") (class "Default")
      (node (ref "OK1") (pin "2") (pinfunction "C_2") (pintype "passive"))
      (node (ref "R2") (pin "1") (pinfunction "1_1") (pintype "passive"))
    )
    (net (code "49") (name "Net-(OK2-A1)") (class "Default")
      (node (ref "OK2") (pin "4") (pinfunction "A1_4") (pintype "passive"))
      (node (ref "Q1") (pin "G") (pinfunction "G_G") (pintype "passive"))
      (node (ref "R1") (pin "2") (pinfunction "2_2") (pintype "passive"))
    )
    (net (code "50") (name "Net-(OK2-A2)") (class "Default")
      (node (ref "OK2") (pin "6") (pinfunction "A2_6") (pintype "passive"))
      (node (ref "R6") (pin "1") (pinfunction "1_1") (pintype "passive"))
    )
    (net (code "51") (name "Net-(OK2-C)") (class "Default")
      (node (ref "OK2") (pin "2") (pinfunction "C_2") (pintype "passive"))
      (node (ref "R7") (pin "1") (pinfunction "1_1") (pintype "passive"))
    )
    (net (code "52") (name "Net-(OK3-A)") (class "Default")
      (node (ref "OK3") (pin "1") (pinfunction "A_1") (pintype "passive"))
      (node (ref "R32") (pin "2") (pinfunction "2_2") (pintype "passive"))
      (node (ref "R35") (pin "1") (pinfunction "1_1") (pintype "passive"))
    )
    (net (code "53") (name "Net-(Q4-D)") (class "Default")
      (node (ref "Q4") (pin "3") (pinfunction "D_3") (pintype "passive"))
      (node (ref "R7") (pin "2") (pinfunction "2_2") (pintype "passive"))
    )
    (net (code "54") (name "Net-(Q5-D)") (class "Default")
      (node (ref "C7") (pin "1") (pinfunction "1_1") (pintype "passive"))
      (node (ref "Q5") (pin "MB") (pinfunction "D_MB") (pintype "passive"))
      (node (ref "R11") (pin "1") (pinfunction "1_1") (pintype "passive"))
    )
    (net (code "55") (name "Net-(Q5-G)") (class "Default")
      (node (ref "C7") (pin "2") (pinfunction "2_2") (pintype "passive"))
      (node (ref "Q5") (pin "4") (pinfunction "G_4") (pintype "passive"))
      (node (ref "R18") (pin "2") (pinfunction "2_2") (pintype "passive"))
    )
    (net (code "56") (name "Net-(Q6-D)") (class "Default")
      (node (ref "Q6") (pin "3") (pinfunction "D_3") (pintype "passive"))
      (node (ref "R15") (pin "2") (pinfunction "2_2") (pintype "passive"))
    )
    (net (code "57") (name "Net-(R22-Pad2)") (class "Default")
      (node (ref "R22") (pin "2") (pinfunction "2_2") (pintype "passive"))
      (node (ref "R24") (pin "2") (pinfunction "2_2") (pintype "passive"))
    )
    (net (code "58") (name "Net-(R23-Pad2)") (class "Default")
      (node (ref "R23") (pin "2") (pinfunction "2_2") (pintype "passive"))
      (node (ref "R26") (pin "1") (pinfunction "1_1") (pintype "passive"))
    )
    (net (code "59") (name "Net-(R26-Pad2)") (class "Default")
      (node (ref "R26") (pin "2") (pinfunction "2_2") (pintype "passive"))
      (node (ref "R29") (pin "1") (pinfunction "1_1") (pintype "passive"))
    )
    (net (code "60") (name "Net-(R33-Pad1)") (class "Default")
      (node (ref "R33") (pin "1") (pinfunction "1_1") (pintype "passive"))
      (node (ref "R37") (pin "2") (pinfunction "2_2") (pintype "passive"))
    )
    (net (code "61") (name "Net-(TR1-P1_DOT)") (class "Default")
      (node (ref "D2") (pin "A") (pinfunction "A_A") (pintype "passive"))
      (node (ref "IC3") (pin "13") (pinfunction "DRAIN_13") (pintype "output"))
      (node (ref "IC3") (pin "14") (pinfunction "DRAIN_14") (pintype "output"))
      (node (ref "IC3") (pin "15") (pinfunction "DRAIN_15") (pintype "output"))
      (node (ref "IC3") (pin "16") (pinfunction "DRAIN_16") (pintype "output"))
      (node (ref "TR1") (pin "4") (pinfunction "P1_DOT_4") (pintype "passive"))
    )
    (net (code "62") (name "Net-(VAR1-P$1)") (class "Default")
      (node (ref "SAR1") (pin "P$1") (pinfunction "P$1_P$1") (pintype "bidirectional"))
      (node (ref "VAR1") (pin "1") (pinfunction "P$1_1") (pintype "bidirectional"))
      (node (ref "VAR2") (pin "2") (pinfunction "P$2_2") (pintype "bidirectional"))
    )
    (net (code "63") (name "Net-(X3H-1)") (class "Default")
      (node (ref "JP2") (pin "NC") (pinfunction "NC_NC") (pintype "passive"))
      (node (ref "X3") (pin "16") (pinfunction "1_16") (pintype "passive"))
    )
    (net (code "64") (name "Net-(X4A-S)") (class "Default")
      (node (ref "C3") (pin "2") (pinfunction "2_2") (pintype "passive"))
      (node (ref "C5") (pin "2") (pinfunction "2_2") (pintype "passive"))
      (node (ref "R11") (pin "2") (pinfunction "2_2") (pintype "passive"))
      (node (ref "X4") (pin "1") (pinfunction "S_1") (pintype "passive"))
      (node (ref "X5") (pin "1") (pinfunction "S_1") (pintype "passive"))
    )
    (net (code "65") (name "PE") (class "Default")
      (node (ref "J1") (pin "PE") (pinfunction "PE_PE") (pintype "bidirectional"))
      (node (ref "J2") (pin "P$1") (pinfunction "P$1_P$1") (pintype "bidirectional"))
      (node (ref "J2") (pin "P$2") (pinfunction "P$1_P$2") (pintype "bidirectional"))
      (node (ref "J3") (pin "P$1") (pinfunction "P$1_P$1") (pintype "bidirectional"))
      (node (ref "J3") (pin "P$2") (pinfunction "P$1_P$2") (pintype "bidirectional"))
      (node (ref "J4") (pin "P$1") (pinfunction "P$1_P$1") (pintype "bidirectional"))
      (node (ref "J4") (pin "P$2") (pinfunction "P$1_P$2") (pintype "bidirectional"))
      (node (ref "J5") (pin "1") (pinfunction "1_1") (pintype "passive"))
      (node (ref "J5") (pin "NC1") (pinfunction "1_NC1") (pintype "passive"))
      (node (ref "J5") (pin "NC2") (pinfunction "1_NC2") (pintype "passive"))
      (node (ref "J5") (pin "NC3") (pinfunction "1_NC3") (pintype "passive"))
      (node (ref "J5") (pin "NC4") (pinfunction "1_NC4") (pintype "passive"))
      (node (ref "JP3") (pin "NC") (pinfunction "NC_NC") (pintype "passive"))
      (node (ref "SAR1") (pin "P$2") (pinfunction "P$2_P$2") (pintype "bidirectional"))
      (node (ref "SW1") (pin "PE1") (pinfunction "PE_PE1") (pintype "power_in"))
      (node (ref "SW1") (pin "PE2") (pinfunction "PE_PE2") (pintype "power_in"))
      (node (ref "X1") (pin "3") (pinfunction "1_3") (pintype "passive"))
      (node (ref "X1") (pin "6") (pinfunction "1_6") (pintype "passive"))
      (node (ref "X2") (pin "3") (pinfunction "1_3") (pintype "passive"))
      (node (ref "X3") (pin "1") (pinfunction "1_1") (pintype "passive"))
      (node (ref "X3") (pin "2") (pinfunction "1_2") (pintype "passive"))
      (node (ref "ZD1") (pin "C") (pinfunction "1_C") (pintype "passive"))
      (node (ref "ZD2") (pin "C") (pinfunction "1_C") (pintype "passive"))
    )
    (net (code "66") (name "PWM_OUT") (class "Default")
      (node (ref "IC1") (pin "6") (pinfunction "PWM_6") (pintype "output"))
      (node (ref "R14") (pin "2") (pinfunction "2_2") (pintype "passive"))
      (node (ref "R18") (pin "1") (pinfunction "1_1") (pintype "passive"))
      (node (ref "X4") (pin "4") (pinfunction "S_4") (pintype "passive"))
      (node (ref "X5") (pin "4") (pinfunction "S_4") (pintype "passive"))
    )
    (net (code "67") (name "PWR_DIRECT") (class "Default")
      (node (ref "Q3") (pin "1") (pinfunction "G_1") (pintype "passive"))
      (node (ref "R5") (pin "2") (pinfunction "2_2") (pintype "passive"))
      (node (ref "X3") (pin "12") (pinfunction "1_12") (pintype "passive"))
    )
    (net (code "68") (name "PWR_DIR_OUT") (class "Default")
      (node (ref "Q3") (pin "3") (pinfunction "D_3") (pintype "passive"))
      (node (ref "Q6") (pin "1") (pinfunction "G_1") (pintype "passive"))
      (node (ref "R16") (pin "2") (pinfunction "2_2") (pintype "passive"))
      (node (ref "R2") (pin "2") (pinfunction "2_2") (pintype "passive"))
    )
    (net (code "69") (name "PWR_SSTART") (class "Default")
      (node (ref "Q4") (pin "1") (pinfunction "G_1") (pintype "passive"))
      (node (ref "R10") (pin "2") (pinfunction "2_2") (pintype "passive"))
      (node (ref "X3") (pin "11") (pinfunction "1_11") (pintype "passive"))
    )
    (net (code "70") (name "SSCL") (class "Default")
      (node (ref "IC1") (pin "15") (pinfunction "SCL_15") (pintype "input"))
      (node (ref "X3") (pin "13") (pinfunction "1_13") (pintype "passive"))
    )
    (net (code "71") (name "SSDA") (class "Default")
      (node (ref "IC1") (pin "14") (pinfunction "SDA_14") (pintype "bidirectional"))
      (node (ref "X3") (pin "14") (pinfunction "1_14") (pintype "passive"))
    )
    (net (code "72") (name "TEMP1_N") (class "Default")
      (node (ref "C9") (pin "2") (pinfunction "2_2") (pintype "passive"))
      (node (ref "IC1") (pin "2") (pinfunction "DXN_2") (pintype "bidirectional"))
      (node (ref "X6") (pin "2") (pinfunction "S_2") (pintype "passive"))
    )
    (net (code "73") (name "TEMP1_P") (class "Default")
      (node (ref "C9") (pin "1") (pinfunction "1_1") (pintype "passive"))
      (node (ref "IC1") (pin "1") (pinfunction "DXP_1") (pintype "input"))
      (node (ref "X6") (pin "1") (pinfunction "S_1") (pintype "passive"))
    )
    (net (code "74") (name "unconnected-(IC2-BYPASS-Pad4)") (class "Default")
      (node (ref "IC2") (pin "4") (pinfunction "BYPASS_4") (pintype "passive"))
    )
    (net (code "75") (name "unconnected-(KK1-K-PadA2,5)") (class "Default")
      (node (ref "KK1") (pin "A2,5") (pinfunction "K_A2,5") (pintype "passive"))
    )
    (net (code "76") (name "unconnected-(KK1-K-PadB2,5)") (class "Default")
      (node (ref "KK1") (pin "B2,5") (pinfunction "K_B2,5") (pintype "passive"))
    )
    (net (code "77") (name "unconnected-(TR1-P1_MIDDLE-Pad3)") (class "Default")
      (node (ref "TR1") (pin "3") (pinfunction "P1_MIDDLE_3") (pintype "passive"))
    )
  )
)
